# ProPrj_X-Link_OB-RA4M2_M_2024-12-25.net
KiCad netlist of a schematic drawn in EasyEDA Pro
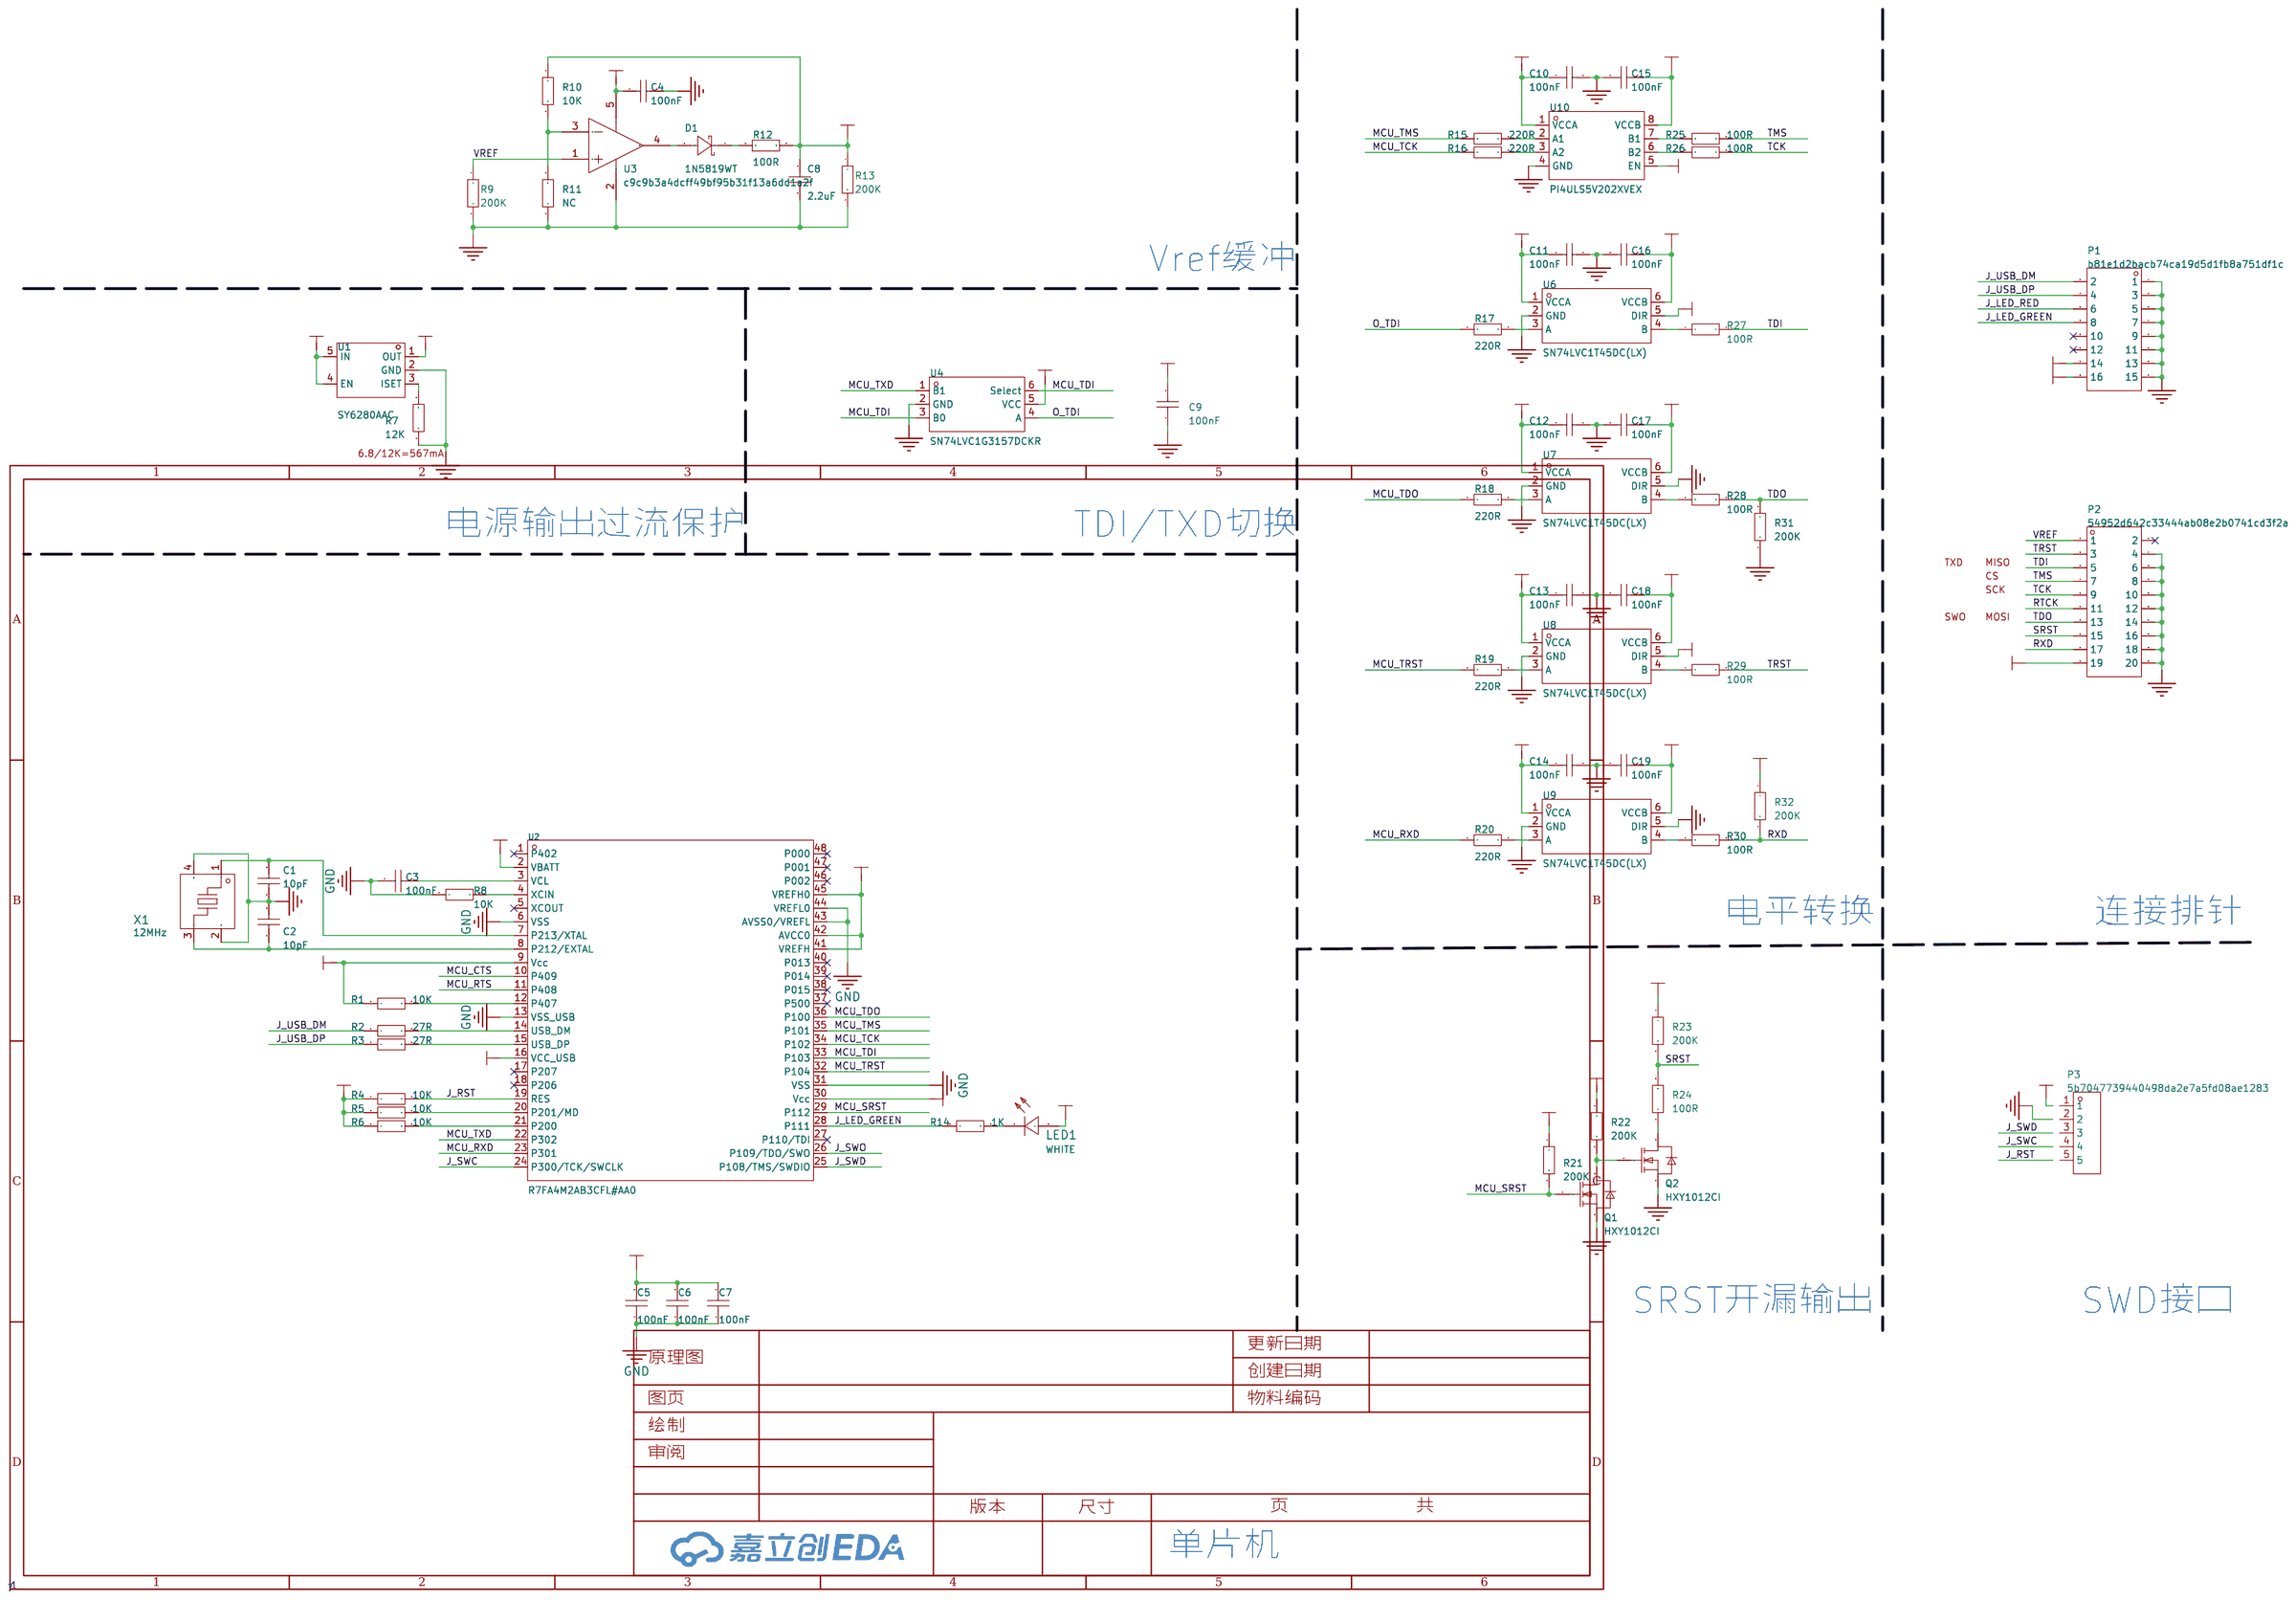
[diagram p0: schematic sheet]

(export (version "E")
  (design (tool "Eeschema 10.0.6"))
  (components
    (comp (ref "C1")
      (value "10pF")
      (footprint "easyedapro:C0805")
      (description "容值:20pF;精度:±5%;额定电压:50V;材质(温度系数):C0G;")
      (fields
        (field (name "Manufacturer Part") "CL21C200JBANNNC")
        (field (name "Manufacturer") "SAMSUNG(三星)")
      )
      (libsource (lib "easyedapro") (part "CL21C200JBANNNC"))
    )
    (comp (ref "C2")
      (value "10pF")
      (footprint "easyedapro:C0805")
      (description "容值:20pF;精度:±5%;额定电压:50V;材质(温度系数):C0G;")
      (fields
        (field (name "Manufacturer Part") "CL21C200JBANNNC")
        (field (name "Manufacturer") "SAMSUNG(三星)")
      )
      (libsource (lib "easyedapro") (part "CL21C200JBANNNC"))
    )
    (comp (ref "C3")
      (value "100nF")
      (footprint "easyedapro:C0805")
      (description "容值:100nF;精度:±10%;额定电压:50V;材质(温度系数):X7R;")
      (fields
        (field (name "Manufacturer Part") "CC0805KRX7R9BB104")
        (field (name "Manufacturer") "YAGEO(国巨)")
      )
      (libsource (lib "easyedapro") (part "CC0805KRX7R9BB104"))
    )
    (comp (ref "C4")
      (value "100nF")
      (footprint "easyedapro:C0402")
      (libsource (lib "easyedapro") (part "C0402"))
    )
    (comp (ref "C5")
      (value "100nF")
      (footprint "easyedapro:C0805")
      (description "容值:100nF;精度:±10%;额定电压:50V;材质(温度系数):X7R;")
      (fields
        (field (name "Manufacturer Part") "CC0805KRX7R9BB104")
        (field (name "Manufacturer") "YAGEO(国巨)")
      )
      (libsource (lib "easyedapro") (part "CC0805KRX7R9BB104"))
    )
    (comp (ref "C6")
      (value "100nF")
      (footprint "easyedapro:C0805")
      (description "容值:100nF;精度:±10%;额定电压:50V;材质(温度系数):X7R;")
      (fields
        (field (name "Manufacturer Part") "CC0805KRX7R9BB104")
        (field (name "Manufacturer") "YAGEO(国巨)")
      )
      (libsource (lib "easyedapro") (part "CC0805KRX7R9BB104"))
    )
    (comp (ref "C7")
      (value "100nF")
      (footprint "easyedapro:C0805")
      (description "容值:100nF;精度:±10%;额定电压:50V;材质(温度系数):X7R;")
      (fields
        (field (name "Manufacturer Part") "CC0805KRX7R9BB104")
        (field (name "Manufacturer") "YAGEO(国巨)")
      )
      (libsource (lib "easyedapro") (part "CC0805KRX7R9BB104"))
    )
    (comp (ref "C8")
      (value "2.2uF")
      (footprint "easyedapro:C0402")
      (libsource (lib "easyedapro") (part "C0402"))
    )
    (comp (ref "C9")
      (value "100nF")
      (footprint "easyedapro:C0603")
      (libsource (lib "easyedapro") (part "C0603"))
    )
    (comp (ref "C10")
      (value "100nF")
      (footprint "easyedapro:C0603")
      (libsource (lib "easyedapro") (part "C0603"))
    )
    (comp (ref "C11")
      (value "100nF")
      (footprint "easyedapro:C0603")
      (libsource (lib "easyedapro") (part "C0603"))
    )
    (comp (ref "C12")
      (value "100nF")
      (footprint "easyedapro:C0603")
      (libsource (lib "easyedapro") (part "C0603"))
    )
    (comp (ref "C13")
      (value "100nF")
      (footprint "easyedapro:C0603")
      (libsource (lib "easyedapro") (part "C0603"))
    )
    (comp (ref "C14")
      (value "100nF")
      (footprint "easyedapro:C0603")
      (libsource (lib "easyedapro") (part "C0603"))
    )
    (comp (ref "C15")
      (value "100nF")
      (footprint "easyedapro:C0603")
      (libsource (lib "easyedapro") (part "C0603"))
    )
    (comp (ref "C16")
      (value "100nF")
      (footprint "easyedapro:C0603")
      (libsource (lib "easyedapro") (part "C0603"))
    )
    (comp (ref "C17")
      (value "100nF")
      (footprint "easyedapro:C0603")
      (libsource (lib "easyedapro") (part "C0603"))
    )
    (comp (ref "C18")
      (value "100nF")
      (footprint "easyedapro:C0603")
      (libsource (lib "easyedapro") (part "C0603"))
    )
    (comp (ref "C19")
      (value "100nF")
      (footprint "easyedapro:C0603")
      (libsource (lib "easyedapro") (part "C0603"))
    )
    (comp (ref "D1")
      (value "1N5819WT")
      (footprint "easyedapro:SOD-523_L1.2-W0.8-LS1.6-RD")
      (description "二极管配置:独立式;正向压降(Vf):600mV@200mA;直流反向耐压(Vr):40V;整流电流:350mA;")
      (fields (field (name "Manufacturer") "Slkor(萨科微)"))
      (libsource (lib "easyedapro") (part "1N5819WT_C5185918"))
    )
    (comp (ref "LED1")
      (value "WHITE")
      (footprint "easyedapro:LED0603")
      (libsource (lib "easyedapro") (part "LED0603"))
    )
    (comp (ref "P1")
      (value "b81e1d2bacb74ca19d5d1fb8a751df1c")
      (footprint "easyedapro:HDR-TH_16P-P1.27-V-M-R2-C8-S1.27-1")
      (libsource (lib "easyedapro") (part "HDR2x8_1.27"))
    )
    (comp (ref "P2")
      (value "54952d642c33444ab08e2b0741cd3f2a")
      (footprint "easyedapro:HDR-TH_20P-P1.27-V-M-R2-C10-S1.27")
      (libsource (lib "easyedapro") (part "HDR2x10_1.27"))
    )
    (comp (ref "P3")
      (value "5b7047739440498da2e7a5fd08ae1283")
      (footprint "easyedapro:HDR-TH_5P-P1.27-V-M")
      (libsource (lib "easyedapro") (part "HDR1x5_1.27"))
    )
    (comp (ref "Q1")
      (value "HXY1012CI")
      (footprint "easyedapro:SOT-523-3_L1.6-W0.8-P0.50-LS1.6-BR")
      (fields (field (name "Manufacturer") "HXY MOSFET(华轩阳电子)"))
      (libsource (lib "easyedapro") (part "HXY1012CI"))
    )
    (comp (ref "Q2")
      (value "HXY1012CI")
      (footprint "easyedapro:SOT-523-3_L1.6-W0.8-P0.50-LS1.6-BR")
      (fields (field (name "Manufacturer") "HXY MOSFET(华轩阳电子)"))
      (libsource (lib "easyedapro") (part "HXY1012CI"))
    )
    (comp (ref "R1")
      (value "10K")
      (footprint "easyedapro:R0805")
      (description "阻值:10kΩ;精度:±1%;功率:125mW;温度系数:±100ppm/°C;最大工作电压:150V;工作温度范围:-55°C~+155°C;")
      (fields (field (name "Manufacturer Part") "RC0805FR-0710KL") (field (name "Manufacturer") "YAGEO(国巨)"))
      (libsource (lib "easyedapro") (part "RC0805FR-0710KL"))
    )
    (comp (ref "R2")
      (value "27R")
      (footprint "easyedapro:R0805")
      (description "电阻类型:厚膜电阻;阻值:27Ω;精度:±1%;功率:125mW;")
      (fields (field (name "Manufacturer Part") "RC0805FR-0727RL") (field (name "Manufacturer") "YAGEO(国巨)"))
      (libsource (lib "easyedapro") (part "RC0805FR-0727RL"))
    )
    (comp (ref "R3")
      (value "27R")
      (footprint "easyedapro:R0805")
      (description "电阻类型:厚膜电阻;阻值:27Ω;精度:±1%;功率:125mW;")
      (fields (field (name "Manufacturer Part") "RC0805FR-0727RL") (field (name "Manufacturer") "YAGEO(国巨)"))
      (libsource (lib "easyedapro") (part "RC0805FR-0727RL"))
    )
    (comp (ref "R4")
      (value "10K")
      (footprint "easyedapro:R0805")
      (description "阻值:10kΩ;精度:±1%;功率:125mW;温度系数:±100ppm/°C;最大工作电压:150V;工作温度范围:-55°C~+155°C;")
      (fields (field (name "Manufacturer Part") "RC0805FR-0710KL") (field (name "Manufacturer") "YAGEO(国巨)"))
      (libsource (lib "easyedapro") (part "RC0805FR-0710KL"))
    )
    (comp (ref "R5")
      (value "10K")
      (footprint "easyedapro:R0805")
      (description "阻值:10kΩ;精度:±1%;功率:125mW;温度系数:±100ppm/°C;最大工作电压:150V;工作温度范围:-55°C~+155°C;")
      (fields (field (name "Manufacturer Part") "RC0805FR-0710KL") (field (name "Manufacturer") "YAGEO(国巨)"))
      (libsource (lib "easyedapro") (part "RC0805FR-0710KL"))
    )
    (comp (ref "R6")
      (value "10K")
      (footprint "easyedapro:R0805")
      (description "阻值:10kΩ;精度:±1%;功率:125mW;温度系数:±100ppm/°C;最大工作电压:150V;工作温度范围:-55°C~+155°C;")
      (fields (field (name "Manufacturer Part") "RC0805FR-0710KL") (field (name "Manufacturer") "YAGEO(国巨)"))
      (libsource (lib "easyedapro") (part "RC0805FR-0710KL"))
    )
    (comp (ref "R7")
      (value "12K")
      (footprint "easyedapro:R0603")
      (libsource (lib "easyedapro") (part "R0603"))
    )
    (comp (ref "R8")
      (value "10K")
      (footprint "easyedapro:R0805")
      (description "阻值:10kΩ;精度:±1%;功率:125mW;温度系数:±100ppm/°C;最大工作电压:150V;工作温度范围:-55°C~+155°C;")
      (fields (field (name "Manufacturer Part") "RC0805FR-0710KL") (field (name "Manufacturer") "YAGEO(国巨)"))
      (libsource (lib "easyedapro") (part "RC0805FR-0710KL"))
    )
    (comp (ref "R9")
      (value "200K")
      (footprint "easyedapro:R0402")
      (libsource (lib "easyedapro") (part "R0402"))
    )
    (comp (ref "R10")
      (value "10K")
      (footprint "easyedapro:R0402")
      (libsource (lib "easyedapro") (part "R0402"))
    )
    (comp (ref "R11")
      (value "NC")
      (footprint "easyedapro:R0402")
      (libsource (lib "easyedapro") (part "R0402"))
    )
    (comp (ref "R12")
      (value "100R")
      (footprint "easyedapro:R0402")
      (libsource (lib "easyedapro") (part "R0402"))
    )
    (comp (ref "R13")
      (value "200K")
      (footprint "easyedapro:R0402")
      (libsource (lib "easyedapro") (part "R0402"))
    )
    (comp (ref "R14")
      (value "1K")
      (footprint "easyedapro:R0805")
      (description "电阻类型:厚膜电阻;阻值:5.1kΩ;精度:±1%;功率:125mW;")
      (fields
        (field (name "Manufacturer Part") "0805W8F5101T5E")
        (field (name "Manufacturer") "UNI-ROYAL(厚声)")
      )
      (libsource (lib "easyedapro") (part "0805W8F5101T5E"))
    )
    (comp (ref "R15") (value "220R") (libsource (lib "easyedapro") (part "电阻")))
    (comp (ref "R16") (value "220R") (libsource (lib "easyedapro") (part "电阻")))
    (comp (ref "R17")
      (value "220R")
      (footprint "easyedapro:R0603")
      (libsource (lib "easyedapro") (part "R0603"))
    )
    (comp (ref "R18")
      (value "220R")
      (footprint "easyedapro:R0603")
      (libsource (lib "easyedapro") (part "R0603"))
    )
    (comp (ref "R19")
      (value "220R")
      (footprint "easyedapro:R0603")
      (libsource (lib "easyedapro") (part "R0603"))
    )
    (comp (ref "R20")
      (value "220R")
      (footprint "easyedapro:R0603")
      (libsource (lib "easyedapro") (part "R0603"))
    )
    (comp (ref "R21") (value "200K") (libsource (lib "easyedapro") (part "电阻")))
    (comp (ref "R22") (value "200K") (libsource (lib "easyedapro") (part "电阻")))
    (comp (ref "R23") (value "200K") (libsource (lib "easyedapro") (part "电阻")))
    (comp (ref "R24") (value "100R") (libsource (lib "easyedapro") (part "电阻")))
    (comp (ref "R25") (value "100R") (libsource (lib "easyedapro") (part "电阻")))
    (comp (ref "R26") (value "100R") (libsource (lib "easyedapro") (part "电阻")))
    (comp (ref "R27")
      (value "100R")
      (footprint "easyedapro:R0603")
      (libsource (lib "easyedapro") (part "R0603"))
    )
    (comp (ref "R28")
      (value "100R")
      (footprint "easyedapro:R0603")
      (libsource (lib "easyedapro") (part "R0603"))
    )
    (comp (ref "R29")
      (value "100R")
      (footprint "easyedapro:R0603")
      (libsource (lib "easyedapro") (part "R0603"))
    )
    (comp (ref "R30")
      (value "100R")
      (footprint "easyedapro:R0603")
      (libsource (lib "easyedapro") (part "R0603"))
    )
    (comp (ref "R31")
      (value "200K")
      (footprint "easyedapro:R0603")
      (libsource (lib "easyedapro") (part "R0603"))
    )
    (comp (ref "R32")
      (value "200K")
      (footprint "easyedapro:R0603")
      (libsource (lib "easyedapro") (part "R0603"))
    )
    (comp (ref "U1")
      (value "SY6280AAC")
      (footprint "easyedapro:SOT-23-5_L3.0-W1.7-P0.95-LS2.8-BL")
      (description "低能耗配电开关")
      (fields (field (name "Manufacturer") "silergy(矽力杰)"))
      (libsource (lib "easyedapro") (part "SY6280AAC"))
    )
    (comp (ref "U2")
      (value "R7FA4M2AB3CFL#AA0")
      (footprint "easyedapro:LQFP-48_L7.0-W7.0-P0.50-LS9.0-BL")
      (description "CPU内核:ARM-M系列;CPU最大主频:100MHz;工作电压范围:2.7V~3.6V;程序存储容量:254KB;GPIO端口数量:30;")
      (fields (field (name "Manufacturer") "RENESAS(瑞萨)/IDT"))
      (libsource (lib "easyedapro") (part "R7FA4M2AB3CFL#AA0"))
    )
    (comp (ref "U3")
      (value "c9c9b3a4dcff49bf95b31f13a6dd1a2f")
      (footprint "easyedapro:SOT-23-5_L2.9-W1.6-P0.95-LS2.8-BR")
      (description "轨到轨输入输出单运放")
      (fields (field (name "Manufacturer Part") "LMV321"))
      (libsource (lib "easyedapro") (part "LMV321"))
    )
    (comp (ref "U4")
      (value "SN74LVC1G3157DCKR")
      (footprint "easyedapro:SC70-6_L2.1-W1.3-P0.65-LS2.3-BL")
      (description "开关电路:单刀双掷(SPDT)-常开/常闭;通道数:1;导通电阻(Ron@VCC):7Ω;")
      (fields (field (name "Manufacturer") "UMW(友台半导体)"))
      (libsource (lib "easyedapro") (part "SN74LVC1G3157DCKR-1"))
    )
    (comp (ref "U6")
      (value "SN74LVC1T45DC(LX)")
      (footprint "easyedapro:SC-70-6_L2.2-W1.3-P0.65-LS2.1-BR")
      (description "电压(VCCA):1.65V~5.5V;电压(VCCB):1.65V~5.5V;电路数:1;每个电路通道数:1;")
      (fields (field (name "Manufacturer") "LX(灵星芯微)"))
      (libsource (lib "easyedapro") (part "74LVC1T45DW-7"))
    )
    (comp (ref "U7")
      (value "SN74LVC1T45DC(LX)")
      (footprint "easyedapro:SC-70-6_L2.2-W1.3-P0.65-LS2.1-BR")
      (description "电压(VCCA):1.65V~5.5V;电压(VCCB):1.65V~5.5V;电路数:1;每个电路通道数:1;")
      (fields (field (name "Manufacturer") "LX(灵星芯微)"))
      (libsource (lib "easyedapro") (part "74LVC1T45DW-7"))
    )
    (comp (ref "U8")
      (value "SN74LVC1T45DC(LX)")
      (footprint "easyedapro:SC-70-6_L2.2-W1.3-P0.65-LS2.1-BR")
      (description "电压(VCCA):1.65V~5.5V;电压(VCCB):1.65V~5.5V;电路数:1;每个电路通道数:1;")
      (fields (field (name "Manufacturer") "LX(灵星芯微)"))
      (libsource (lib "easyedapro") (part "74LVC1T45DW-7"))
    )
    (comp (ref "U9")
      (value "SN74LVC1T45DC(LX)")
      (footprint "easyedapro:SC-70-6_L2.2-W1.3-P0.65-LS2.1-BR")
      (description "电压(VCCA):1.65V~5.5V;电压(VCCB):1.65V~5.5V;电路数:1;每个电路通道数:1;")
      (fields (field (name "Manufacturer") "LX(灵星芯微)"))
      (libsource (lib "easyedapro") (part "74LVC1T45DW-7"))
    )
    (comp (ref "U10")
      (value "PI4ULS5V202XVEX")
      (footprint "easyedapro:UDFN-8_L1.6-W1.2-P0.40-BL")
      (description "数据速率:20Mbps;电压(VCCA):1.2V~5.5V;电压(VCCB):1.2V~5.5V;电路数:1;每个电路通道数:2;")
      (fields (field (name "Manufacturer") "DIODES(美台)"))
      (libsource (lib "easyedapro") (part "PI4ULS5V202XVEX"))
    )
    (comp (ref "X1")
      (value "12MHz")
      (footprint "easyedapro:CRYSTAL-SMD_4P-L3.2-W2.5-BL-A")
      (libsource (lib "easyedapro") (part "XTAL3225"))
    )
  )
  (nets
    (net (code "1") (name "/J_LED_GREEN") (class "Default")
      (node (ref "P1") (pin "8") (pinfunction "8_8") (pintype "unspecified"))
      (node (ref "R14") (pin "1") (pinfunction "1_1") (pintype "input"))
      (node (ref "U2") (pin "28") (pinfunction "P111_28") (pintype "input"))
    )
    (net (code "2") (name "/J_LED_RED") (class "Default")
      (node (ref "P1") (pin "6") (pinfunction "6_6") (pintype "unspecified"))
    )
    (net (code "3") (name "/J_RST") (class "Default")
      (node (ref "R4") (pin "2") (pinfunction "2_2") (pintype "input"))
      (node (ref "U2") (pin "19") (pinfunction "RES_19") (pintype "input"))
    )
    (net (code "4") (name "/J_SWC") (class "Default")
      (node (ref "U2") (pin "24") (pinfunction "P300/TCK/SWCLK_24") (pintype "input"))
    )
    (net (code "5") (name "/J_SWD") (class "Default")
      (node (ref "U2") (pin "25") (pinfunction "P108/TMS/SWDIO_25") (pintype "input"))
    )
    (net (code "6") (name "/J_SWO") (class "Default")
      (node (ref "U2") (pin "26") (pinfunction "P109/TDO/SWO_26") (pintype "input"))
    )
    (net (code "7") (name "/J_USB_DM") (class "Default")
      (node (ref "P1") (pin "2") (pinfunction "2_2") (pintype "unspecified"))
      (node (ref "R2") (pin "1") (pinfunction "1_1") (pintype "input"))
    )
    (net (code "8") (name "/J_USB_DP") (class "Default")
      (node (ref "P1") (pin "4") (pinfunction "4_4") (pintype "unspecified"))
      (node (ref "R3") (pin "1") (pinfunction "1_1") (pintype "input"))
    )
    (net (code "9") (name "/MCU_CTS") (class "Default")
      (node (ref "U2") (pin "10") (pinfunction "P409_10") (pintype "input"))
    )
    (net (code "10") (name "/MCU_RTS") (class "Default")
      (node (ref "U2") (pin "11") (pinfunction "P408_11") (pintype "input"))
    )
    (net (code "11") (name "/MCU_RXD") (class "Default")
      (node (ref "R20") (pin "1") (pinfunction "1_1") (pintype "input"))
      (node (ref "U2") (pin "23") (pinfunction "P301_23") (pintype "input"))
    )
    (net (code "12") (name "/MCU_SRST") (class "Default")
      (node (ref "Q1") (pin "1") (pinfunction "G_1") (pintype "unspecified"))
      (node (ref "R21") (pin "2") (pinfunction "2_2") (pintype "input"))
      (node (ref "U2") (pin "29") (pinfunction "P112_29") (pintype "input"))
    )
    (net (code "13") (name "/MCU_TCK") (class "Default")
      (node (ref "R16") (pin "1") (pinfunction "1_1") (pintype "input"))
      (node (ref "U2") (pin "34") (pinfunction "P102_34") (pintype "input"))
    )
    (net (code "14") (name "/MCU_TDI") (class "Default")
      (node (ref "U2") (pin "33") (pinfunction "P103_33") (pintype "input"))
      (node (ref "U4") (pin "3") (pinfunction "B0_3") (pintype "unspecified"))
      (node (ref "U4") (pin "6") (pinfunction "Select_6") (pintype "unspecified"))
    )
    (net (code "15") (name "/MCU_TDO") (class "Default")
      (node (ref "R18") (pin "1") (pinfunction "1_1") (pintype "input"))
      (node (ref "U2") (pin "36") (pinfunction "P100_36") (pintype "input"))
    )
    (net (code "16") (name "/MCU_TMS") (class "Default")
      (node (ref "R15") (pin "1") (pinfunction "1_1") (pintype "input"))
      (node (ref "U2") (pin "35") (pinfunction "P101_35") (pintype "input"))
    )
    (net (code "17") (name "/MCU_TRST") (class "Default")
      (node (ref "R19") (pin "1") (pinfunction "1_1") (pintype "input"))
      (node (ref "U2") (pin "32") (pinfunction "P104_32") (pintype "input"))
    )
    (net (code "18") (name "/MCU_TXD") (class "Default")
      (node (ref "U2") (pin "22") (pinfunction "P302_22") (pintype "input"))
      (node (ref "U4") (pin "1") (pinfunction "B1_1") (pintype "unspecified"))
    )
    (net (code "19") (name "/O_TDI") (class "Default")
      (node (ref "R17") (pin "1") (pinfunction "1_1") (pintype "input"))
      (node (ref "U4") (pin "4") (pinfunction "A_4") (pintype "unspecified"))
    )
    (net (code "20") (name "/RTCK") (class "Default")
      (node (ref "P2") (pin "11") (pinfunction "11_11") (pintype "unspecified"))
    )
    (net (code "21") (name "/RXD") (class "Default")
      (node (ref "P2") (pin "17") (pinfunction "17_17") (pintype "unspecified"))
      (node (ref "R30") (pin "2") (pinfunction "2_2") (pintype "input"))
      (node (ref "R32") (pin "2") (pinfunction "2_2") (pintype "input"))
    )
    (net (code "22") (name "/SRST") (class "Default")
      (node (ref "P2") (pin "15") (pinfunction "15_15") (pintype "unspecified"))
      (node (ref "R23") (pin "2") (pinfunction "2_2") (pintype "input"))
      (node (ref "R24") (pin "2") (pinfunction "2_2") (pintype "input"))
    )
    (net (code "23") (name "/TCK") (class "Default")
      (node (ref "P2") (pin "9") (pinfunction "9_9") (pintype "unspecified"))
      (node (ref "R26") (pin "2") (pinfunction "2_2") (pintype "input"))
    )
    (net (code "24") (name "/TDI") (class "Default")
      (node (ref "P2") (pin "5") (pinfunction "5_5") (pintype "unspecified"))
      (node (ref "R27") (pin "2") (pinfunction "2_2") (pintype "input"))
    )
    (net (code "25") (name "/TDO") (class "Default")
      (node (ref "P2") (pin "13") (pinfunction "13_13") (pintype "unspecified"))
      (node (ref "R28") (pin "2") (pinfunction "2_2") (pintype "input"))
      (node (ref "R31") (pin "2") (pinfunction "2_2") (pintype "input"))
    )
    (net (code "26") (name "/TMS") (class "Default")
      (node (ref "P2") (pin "7") (pinfunction "7_7") (pintype "unspecified"))
      (node (ref "R25") (pin "2") (pinfunction "2_2") (pintype "input"))
    )
    (net (code "27") (name "/TRST") (class "Default")
      (node (ref "P2") (pin "3") (pinfunction "3_3") (pintype "unspecified"))
      (node (ref "R29") (pin "2") (pinfunction "2_2") (pintype "input"))
    )
    (net (code "28") (name "/VREF") (class "Default")
      (node (ref "P2") (pin "1") (pinfunction "1_1") (pintype "unspecified"))
      (node (ref "R9") (pin "1") (pinfunction "1_1") (pintype "input"))
      (node (ref "U3") (pin "1") (pinfunction "+IN_1") (pintype "unspecified"))
    )
    (net (code "29") (name "3.3V") (class "Default")
      (node (ref "C10") (pin "1") (pinfunction "1_1") (pintype "input"))
      (node (ref "C11") (pin "1") (pinfunction "1_1") (pintype "input"))
      (node (ref "C12") (pin "1") (pinfunction "1_1") (pintype "input"))
      (node (ref "C13") (pin "1") (pinfunction "1_1") (pintype "input"))
      (node (ref "C14") (pin "1") (pinfunction "1_1") (pintype "input"))
      (node (ref "C5") (pin "2") (pinfunction "2_2") (pintype "input"))
      (node (ref "C6") (pin "2") (pinfunction "2_2") (pintype "input"))
      (node (ref "C7") (pin "2") (pinfunction "2_2") (pintype "input"))
      (node (ref "C9") (pin "2") (pinfunction "2_2") (pintype "input"))
      (node (ref "LED1") (pin "2") (pinfunction "+_2") (pintype "input"))
      (node (ref "P1") (pin "14") (pinfunction "14_14") (pintype "unspecified"))
      (node (ref "R1") (pin "1") (pinfunction "1_1") (pintype "input"))
      (node (ref "R21") (pin "1") (pinfunction "1_1") (pintype "input"))
      (node (ref "R22") (pin "1") (pinfunction "1_1") (pintype "input"))
      (node (ref "R4") (pin "1") (pinfunction "1_1") (pintype "input"))
      (node (ref "R5") (pin "1") (pinfunction "1_1") (pintype "input"))
      (node (ref "R6") (pin "1") (pinfunction "1_1") (pintype "input"))
      (node (ref "U10") (pin "1") (pinfunction "VCCA_1") (pintype "unspecified"))
      (node (ref "U10") (pin "5") (pinfunction "EN_5") (pintype "unspecified"))
      (node (ref "U2") (pin "16") (pinfunction "VCC_USB_16") (pintype "input"))
      (node (ref "U2") (pin "2") (pinfunction "VBATT_2") (pintype "input"))
      (node (ref "U2") (pin "30") (pinfunction "Vcc_30") (pintype "input"))
      (node (ref "U2") (pin "41") (pinfunction "VREFH_41") (pintype "input"))
      (node (ref "U2") (pin "42") (pinfunction "AVCC0_42") (pintype "input"))
      (node (ref "U2") (pin "45") (pinfunction "VREFH0_45") (pintype "input"))
      (node (ref "U2") (pin "9") (pinfunction "Vcc_9") (pintype "input"))
      (node (ref "U4") (pin "5") (pinfunction "VCC_5") (pintype "unspecified"))
      (node (ref "U6") (pin "1") (pinfunction "VCCA_1") (pintype "unspecified"))
      (node (ref "U6") (pin "5") (pinfunction "DIR_5") (pintype "unspecified"))
      (node (ref "U7") (pin "1") (pinfunction "VCCA_1") (pintype "unspecified"))
      (node (ref "U8") (pin "1") (pinfunction "VCCA_1") (pintype "unspecified"))
      (node (ref "U8") (pin "5") (pinfunction "DIR_5") (pintype "unspecified"))
      (node (ref "U9") (pin "1") (pinfunction "VCCA_1") (pintype "unspecified"))
    )
    (net (code "30") (name "5V") (class "Default")
      (node (ref "C4") (pin "1") (pinfunction "1_1") (pintype "input"))
      (node (ref "P1") (pin "16") (pinfunction "16_16") (pintype "unspecified"))
      (node (ref "U1") (pin "4") (pinfunction "EN_4") (pintype "unspecified"))
      (node (ref "U1") (pin "5") (pinfunction "IN_5") (pintype "unspecified"))
      (node (ref "U3") (pin "5") (pinfunction "VCC+_5") (pintype "unspecified"))
    )
    (net (code "31") (name "5V_OUT") (class "Default")
      (node (ref "P2") (pin "19") (pinfunction "19_19") (pintype "unspecified"))
      (node (ref "U1") (pin "1") (pinfunction "OUT_1") (pintype "unspecified"))
    )
    (net (code "32") (name "GND") (class "Default")
      (node (ref "C1") (pin "1") (pinfunction "1_1") (pintype "input"))
      (node (ref "C10") (pin "2") (pinfunction "2_2") (pintype "input"))
      (node (ref "C11") (pin "2") (pinfunction "2_2") (pintype "input"))
      (node (ref "C12") (pin "2") (pinfunction "2_2") (pintype "input"))
      (node (ref "C13") (pin "2") (pinfunction "2_2") (pintype "input"))
      (node (ref "C14") (pin "2") (pinfunction "2_2") (pintype "input"))
      (node (ref "C15") (pin "1") (pinfunction "1_1") (pintype "input"))
      (node (ref "C16") (pin "1") (pinfunction "1_1") (pintype "input"))
      (node (ref "C17") (pin "1") (pinfunction "1_1") (pintype "input"))
      (node (ref "C18") (pin "1") (pinfunction "1_1") (pintype "input"))
      (node (ref "C19") (pin "1") (pinfunction "1_1") (pintype "input"))
      (node (ref "C2") (pin "2") (pinfunction "2_2") (pintype "input"))
      (node (ref "C3") (pin "1") (pinfunction "1_1") (pintype "input"))
      (node (ref "C4") (pin "2") (pinfunction "2_2") (pintype "input"))
      (node (ref "C5") (pin "1") (pinfunction "1_1") (pintype "input"))
      (node (ref "C6") (pin "1") (pinfunction "1_1") (pintype "input"))
      (node (ref "C7") (pin "1") (pinfunction "1_1") (pintype "input"))
      (node (ref "C8") (pin "1") (pinfunction "1_1") (pintype "input"))
      (node (ref "C9") (pin "1") (pinfunction "1_1") (pintype "input"))
      (node (ref "P1") (pin "1") (pinfunction "1_1") (pintype "unspecified"))
      (node (ref "P1") (pin "11") (pinfunction "11_11") (pintype "unspecified"))
      (node (ref "P1") (pin "13") (pinfunction "13_13") (pintype "unspecified"))
      (node (ref "P1") (pin "15") (pinfunction "15_15") (pintype "unspecified"))
      (node (ref "P1") (pin "3") (pinfunction "3_3") (pintype "unspecified"))
      (node (ref "P1") (pin "5") (pinfunction "5_5") (pintype "unspecified"))
      (node (ref "P1") (pin "7") (pinfunction "7_7") (pintype "unspecified"))
      (node (ref "P1") (pin "9") (pinfunction "9_9") (pintype "unspecified"))
      (node (ref "P2") (pin "10") (pinfunction "10_10") (pintype "unspecified"))
      (node (ref "P2") (pin "12") (pinfunction "12_12") (pintype "unspecified"))
      (node (ref "P2") (pin "14") (pinfunction "14_14") (pintype "unspecified"))
      (node (ref "P2") (pin "16") (pinfunction "16_16") (pintype "unspecified"))
      (node (ref "P2") (pin "18") (pinfunction "18_18") (pintype "unspecified"))
      (node (ref "P2") (pin "20") (pinfunction "20_20") (pintype "unspecified"))
      (node (ref "P2") (pin "4") (pinfunction "4_4") (pintype "unspecified"))
      (node (ref "P2") (pin "6") (pinfunction "6_6") (pintype "unspecified"))
      (node (ref "P2") (pin "8") (pinfunction "8_8") (pintype "unspecified"))
      (node (ref "Q1") (pin "2") (pinfunction "S_2") (pintype "unspecified"))
      (node (ref "Q2") (pin "2") (pinfunction "S_2") (pintype "unspecified"))
      (node (ref "R11") (pin "1") (pinfunction "1_1") (pintype "input"))
      (node (ref "R13") (pin "2") (pinfunction "2_2") (pintype "input"))
      (node (ref "R31") (pin "1") (pinfunction "1_1") (pintype "input"))
      (node (ref "R7") (pin "1") (pinfunction "1_1") (pintype "input"))
      (node (ref "R8") (pin "1") (pinfunction "1_1") (pintype "input"))
      (node (ref "R9") (pin "2") (pinfunction "2_2") (pintype "input"))
      (node (ref "U1") (pin "2") (pinfunction "GND_2") (pintype "unspecified"))
      (node (ref "U10") (pin "4") (pinfunction "GND_4") (pintype "unspecified"))
      (node (ref "U2") (pin "13") (pinfunction "VSS_USB_13") (pintype "input"))
      (node (ref "U2") (pin "31") (pinfunction "VSS_31") (pintype "input"))
      (node (ref "U2") (pin "43") (pinfunction "AVSS0/VREFL_43") (pintype "input"))
      (node (ref "U2") (pin "44") (pinfunction "VREFL0_44") (pintype "input"))
      (node (ref "U2") (pin "6") (pinfunction "VSS_6") (pintype "input"))
      (node (ref "U3") (pin "2") (pinfunction "GND_2") (pintype "unspecified"))
      (node (ref "U4") (pin "2") (pinfunction "GND_2") (pintype "unspecified"))
      (node (ref "U6") (pin "2") (pinfunction "GND_2") (pintype "unspecified"))
      (node (ref "U7") (pin "2") (pinfunction "GND_2") (pintype "unspecified"))
      (node (ref "U7") (pin "5") (pinfunction "DIR_5") (pintype "unspecified"))
      (node (ref "U8") (pin "2") (pinfunction "GND_2") (pintype "unspecified"))
      (node (ref "U9") (pin "2") (pinfunction "GND_2") (pintype "unspecified"))
      (node (ref "U9") (pin "5") (pinfunction "DIR_5") (pintype "unspecified"))
      (node (ref "X1") (pin "2") (pinfunction "GND_2") (pintype "input"))
      (node (ref "X1") (pin "4") (pinfunction "GND_4") (pintype "input"))
    )
    (net (code "33") (name "Net-(D1-Pad1)") (class "Default")
      (node (ref "D1") (pin "1") (pinfunction "1_1") (pintype "unspecified"))
      (node (ref "R12") (pin "2") (pinfunction "2_2") (pintype "input"))
    )
    (net (code "34") (name "Net-(LED1--)") (class "Default")
      (node (ref "LED1") (pin "1") (pinfunction "-_1") (pintype "input"))
      (node (ref "R14") (pin "2") (pinfunction "2_2") (pintype "input"))
    )
    (net (code "35") (name "Net-(Q1-D)") (class "Default")
      (node (ref "Q1") (pin "3") (pinfunction "D_3") (pintype "unspecified"))
      (node (ref "Q2") (pin "1") (pinfunction "G_1") (pintype "unspecified"))
      (node (ref "R22") (pin "2") (pinfunction "2_2") (pintype "input"))
    )
    (net (code "36") (name "Net-(Q2-D)") (class "Default")
      (node (ref "Q2") (pin "3") (pinfunction "D_3") (pintype "unspecified"))
      (node (ref "R24") (pin "1") (pinfunction "1_1") (pintype "input"))
    )
    (net (code "37") (name "Net-(U1-ISET)") (class "Default")
      (node (ref "R7") (pin "2") (pinfunction "2_2") (pintype "input"))
      (node (ref "U1") (pin "3") (pinfunction "ISET_3") (pintype "unspecified"))
    )
    (net (code "38") (name "Net-(U2-P200)") (class "Default")
      (node (ref "R6") (pin "2") (pinfunction "2_2") (pintype "input"))
      (node (ref "U2") (pin "21") (pinfunction "P200_21") (pintype "input"))
    )
    (net (code "39") (name "Net-(U2-P201{slash}MD)") (class "Default")
      (node (ref "R5") (pin "2") (pinfunction "2_2") (pintype "input"))
      (node (ref "U2") (pin "20") (pinfunction "P201/MD_20") (pintype "input"))
    )
    (net (code "40") (name "Net-(U2-P212{slash}EXTAL)") (class "Default")
      (node (ref "C2") (pin "1") (pinfunction "1_1") (pintype "input"))
      (node (ref "U2") (pin "8") (pinfunction "P212/EXTAL_8") (pintype "input"))
      (node (ref "X1") (pin "3") (pinfunction "3_3") (pintype "input"))
    )
    (net (code "41") (name "Net-(U2-P213{slash}XTAL)") (class "Default")
      (node (ref "C1") (pin "2") (pinfunction "2_2") (pintype "input"))
      (node (ref "U2") (pin "7") (pinfunction "P213/XTAL_7") (pintype "input"))
      (node (ref "X1") (pin "1") (pinfunction "1_1") (pintype "input"))
    )
    (net (code "42") (name "Net-(U2-P407)") (class "Default")
      (node (ref "R1") (pin "2") (pinfunction "2_2") (pintype "input"))
      (node (ref "U2") (pin "12") (pinfunction "P407_12") (pintype "input"))
    )
    (net (code "43") (name "Net-(U2-USB_DM)") (class "Default")
      (node (ref "R2") (pin "2") (pinfunction "2_2") (pintype "input"))
      (node (ref "U2") (pin "14") (pinfunction "USB_DM_14") (pintype "input"))
    )
    (net (code "44") (name "Net-(U2-USB_DP)") (class "Default")
      (node (ref "R3") (pin "2") (pinfunction "2_2") (pintype "input"))
      (node (ref "U2") (pin "15") (pinfunction "USB_DP_15") (pintype "input"))
    )
    (net (code "45") (name "Net-(U2-VCL)") (class "Default")
      (node (ref "C3") (pin "2") (pinfunction "2_2") (pintype "input"))
      (node (ref "U2") (pin "3") (pinfunction "VCL_3") (pintype "input"))
    )
    (net (code "46") (name "Net-(U2-XCIN)") (class "Default")
      (node (ref "R8") (pin "2") (pinfunction "2_2") (pintype "input"))
      (node (ref "U2") (pin "4") (pinfunction "XCIN_4") (pintype "input"))
    )
    (net (code "47") (name "Net-(U3--IN)") (class "Default")
      (node (ref "R10") (pin "2") (pinfunction "2_2") (pintype "input"))
      (node (ref "R11") (pin "2") (pinfunction "2_2") (pintype "input"))
      (node (ref "U3") (pin "3") (pinfunction "-IN_3") (pintype "unspecified"))
    )
    (net (code "48") (name "Net-(U3-OUT)") (class "Default")
      (node (ref "D1") (pin "2") (pinfunction "2_2") (pintype "unspecified"))
      (node (ref "U3") (pin "4") (pinfunction "OUT_4") (pintype "output"))
    )
    (net (code "49") (name "Net-(U6-A)") (class "Default")
      (node (ref "R17") (pin "2") (pinfunction "2_2") (pintype "input"))
      (node (ref "U6") (pin "3") (pinfunction "A_3") (pintype "unspecified"))
    )
    (net (code "50") (name "Net-(U6-B)") (class "Default")
      (node (ref "R27") (pin "1") (pinfunction "1_1") (pintype "input"))
      (node (ref "U6") (pin "4") (pinfunction "B_4") (pintype "unspecified"))
    )
    (net (code "51") (name "Net-(U7-A)") (class "Default")
      (node (ref "R18") (pin "2") (pinfunction "2_2") (pintype "input"))
      (node (ref "U7") (pin "3") (pinfunction "A_3") (pintype "unspecified"))
    )
    (net (code "52") (name "Net-(U7-B)") (class "Default")
      (node (ref "R28") (pin "1") (pinfunction "1_1") (pintype "input"))
      (node (ref "U7") (pin "4") (pinfunction "B_4") (pintype "unspecified"))
    )
    (net (code "53") (name "Net-(U8-A)") (class "Default")
      (node (ref "R19") (pin "2") (pinfunction "2_2") (pintype "input"))
      (node (ref "U8") (pin "3") (pinfunction "A_3") (pintype "unspecified"))
    )
    (net (code "54") (name "Net-(U8-B)") (class "Default")
      (node (ref "R29") (pin "1") (pinfunction "1_1") (pintype "input"))
      (node (ref "U8") (pin "4") (pinfunction "B_4") (pintype "unspecified"))
    )
    (net (code "55") (name "Net-(U9-A)") (class "Default")
      (node (ref "R20") (pin "2") (pinfunction "2_2") (pintype "input"))
      (node (ref "U9") (pin "3") (pinfunction "A_3") (pintype "unspecified"))
    )
    (net (code "56") (name "Net-(U9-B)") (class "Default")
      (node (ref "R30") (pin "1") (pinfunction "1_1") (pintype "input"))
      (node (ref "U9") (pin "4") (pinfunction "B_4") (pintype "unspecified"))
    )
    (net (code "57") (name "Net-(U10-A1)") (class "Default")
      (node (ref "R15") (pin "2") (pinfunction "2_2") (pintype "input"))
      (node (ref "U10") (pin "2") (pinfunction "A1_2") (pintype "unspecified"))
    )
    (net (code "58") (name "Net-(U10-A2)") (class "Default")
      (node (ref "R16") (pin "2") (pinfunction "2_2") (pintype "input"))
      (node (ref "U10") (pin "3") (pinfunction "A2_3") (pintype "unspecified"))
    )
    (net (code "59") (name "Net-(U10-B1)") (class "Default")
      (node (ref "R25") (pin "1") (pinfunction "1_1") (pintype "input"))
      (node (ref "U10") (pin "7") (pinfunction "B1_7") (pintype "unspecified"))
    )
    (net (code "60") (name "Net-(U10-B2)") (class "Default")
      (node (ref "R26") (pin "1") (pinfunction "1_1") (pintype "input"))
      (node (ref "U10") (pin "6") (pinfunction "B2_6") (pintype "unspecified"))
    )
    (net (code "61") (name "VIO") (class "Default")
      (node (ref "C15") (pin "2") (pinfunction "2_2") (pintype "input"))
      (node (ref "C16") (pin "2") (pinfunction "2_2") (pintype "input"))
      (node (ref "C17") (pin "2") (pinfunction "2_2") (pintype "input"))
      (node (ref "C18") (pin "2") (pinfunction "2_2") (pintype "input"))
      (node (ref "C19") (pin "2") (pinfunction "2_2") (pintype "input"))
      (node (ref "C8") (pin "2") (pinfunction "2_2") (pintype "input"))
      (node (ref "R10") (pin "1") (pinfunction "1_1") (pintype "input"))
      (node (ref "R12") (pin "1") (pinfunction "1_1") (pintype "input"))
      (node (ref "R13") (pin "1") (pinfunction "1_1") (pintype "input"))
      (node (ref "R23") (pin "1") (pinfunction "1_1") (pintype "input"))
      (node (ref "R32") (pin "1") (pinfunction "1_1") (pintype "input"))
      (node (ref "U10") (pin "8") (pinfunction "VCCB_8") (pintype "unspecified"))
      (node (ref "U6") (pin "6") (pinfunction "VCCB_6") (pintype "unspecified"))
      (node (ref "U7") (pin "6") (pinfunction "VCCB_6") (pintype "unspecified"))
      (node (ref "U8") (pin "6") (pinfunction "VCCB_6") (pintype "unspecified"))
      (node (ref "U9") (pin "6") (pinfunction "VCCB_6") (pintype "unspecified"))
    )
    (net (code "62") (name "unconnected-(P1-Pad10)") (class "Default")
      (node (ref "P1") (pin "10") (pinfunction "10_10") (pintype "unspecified+no_connect"))
    )
    (net (code "63") (name "unconnected-(P1-Pad12)") (class "Default")
      (node (ref "P1") (pin "12") (pinfunction "12_12") (pintype "unspecified+no_connect"))
    )
    (net (code "64") (name "unconnected-(P2-Pad2)") (class "Default")
      (node (ref "P2") (pin "2") (pinfunction "2_2") (pintype "unspecified+no_connect"))
    )
    (net (code "65") (name "unconnected-(P3-Pad1)") (class "Default")
      (node (ref "P3") (pin "1") (pinfunction "1_1") (pintype "unspecified"))
    )
    (net (code "66") (name "unconnected-(P3-Pad2)") (class "Default")
      (node (ref "P3") (pin "2") (pinfunction "2_2") (pintype "unspecified"))
    )
    (net (code "67") (name "unconnected-(P3-Pad3)") (class "Default")
      (node (ref "P3") (pin "3") (pinfunction "3_3") (pintype "unspecified"))
    )
    (net (code "68") (name "unconnected-(P3-Pad4)") (class "Default")
      (node (ref "P3") (pin "4") (pinfunction "4_4") (pintype "unspecified"))
    )
    (net (code "69") (name "unconnected-(P3-Pad5)") (class "Default")
      (node (ref "P3") (pin "5") (pinfunction "5_5") (pintype "unspecified"))
    )
    (net (code "70") (name "unconnected-(U2-P000-Pad48)") (class "Default")
      (node (ref "U2") (pin "48") (pinfunction "P000_48") (pintype "input+no_connect"))
    )
    (net (code "71") (name "unconnected-(U2-P001-Pad47)") (class "Default")
      (node (ref "U2") (pin "47") (pinfunction "P001_47") (pintype "input+no_connect"))
    )
    (net (code "72") (name "unconnected-(U2-P002-Pad46)") (class "Default")
      (node (ref "U2") (pin "46") (pinfunction "P002_46") (pintype "input+no_connect"))
    )
    (net (code "73") (name "unconnected-(U2-P013-Pad40)") (class "Default")
      (node (ref "U2") (pin "40") (pinfunction "P013_40") (pintype "input+no_connect"))
    )
    (net (code "74") (name "unconnected-(U2-P014-Pad39)") (class "Default")
      (node (ref "U2") (pin "39") (pinfunction "P014_39") (pintype "input+no_connect"))
    )
    (net (code "75") (name "unconnected-(U2-P015-Pad38)") (class "Default")
      (node (ref "U2") (pin "38") (pinfunction "P015_38") (pintype "input+no_connect"))
    )
    (net (code "76") (name "unconnected-(U2-P110{slash}TDI-Pad27)") (class "Default")
      (node (ref "U2") (pin "27") (pinfunction "P110/TDI_27") (pintype "input+no_connect"))
    )
    (net (code "77") (name "unconnected-(U2-P206-Pad18)") (class "Default")
      (node (ref "U2") (pin "18") (pinfunction "P206_18") (pintype "input+no_connect"))
    )
    (net (code "78") (name "unconnected-(U2-P207-Pad17)") (class "Default")
      (node (ref "U2") (pin "17") (pinfunction "P207_17") (pintype "input+no_connect"))
    )
    (net (code "79") (name "unconnected-(U2-P402-Pad1)") (class "Default")
      (node (ref "U2") (pin "1") (pinfunction "P402_1") (pintype "input+no_connect"))
    )
    (net (code "80") (name "unconnected-(U2-P500-Pad37)") (class "Default")
      (node (ref "U2") (pin "37") (pinfunction "P500_37") (pintype "input+no_connect"))
    )
    (net (code "81") (name "unconnected-(U2-XCOUT-Pad5)") (class "Default")
      (node (ref "U2") (pin "5") (pinfunction "XCOUT_5") (pintype "input+no_connect"))
    )
  )
)
